# ADXL345_STEMMA_QT.net
KiCad netlist of a schematic drawn in EAGLE
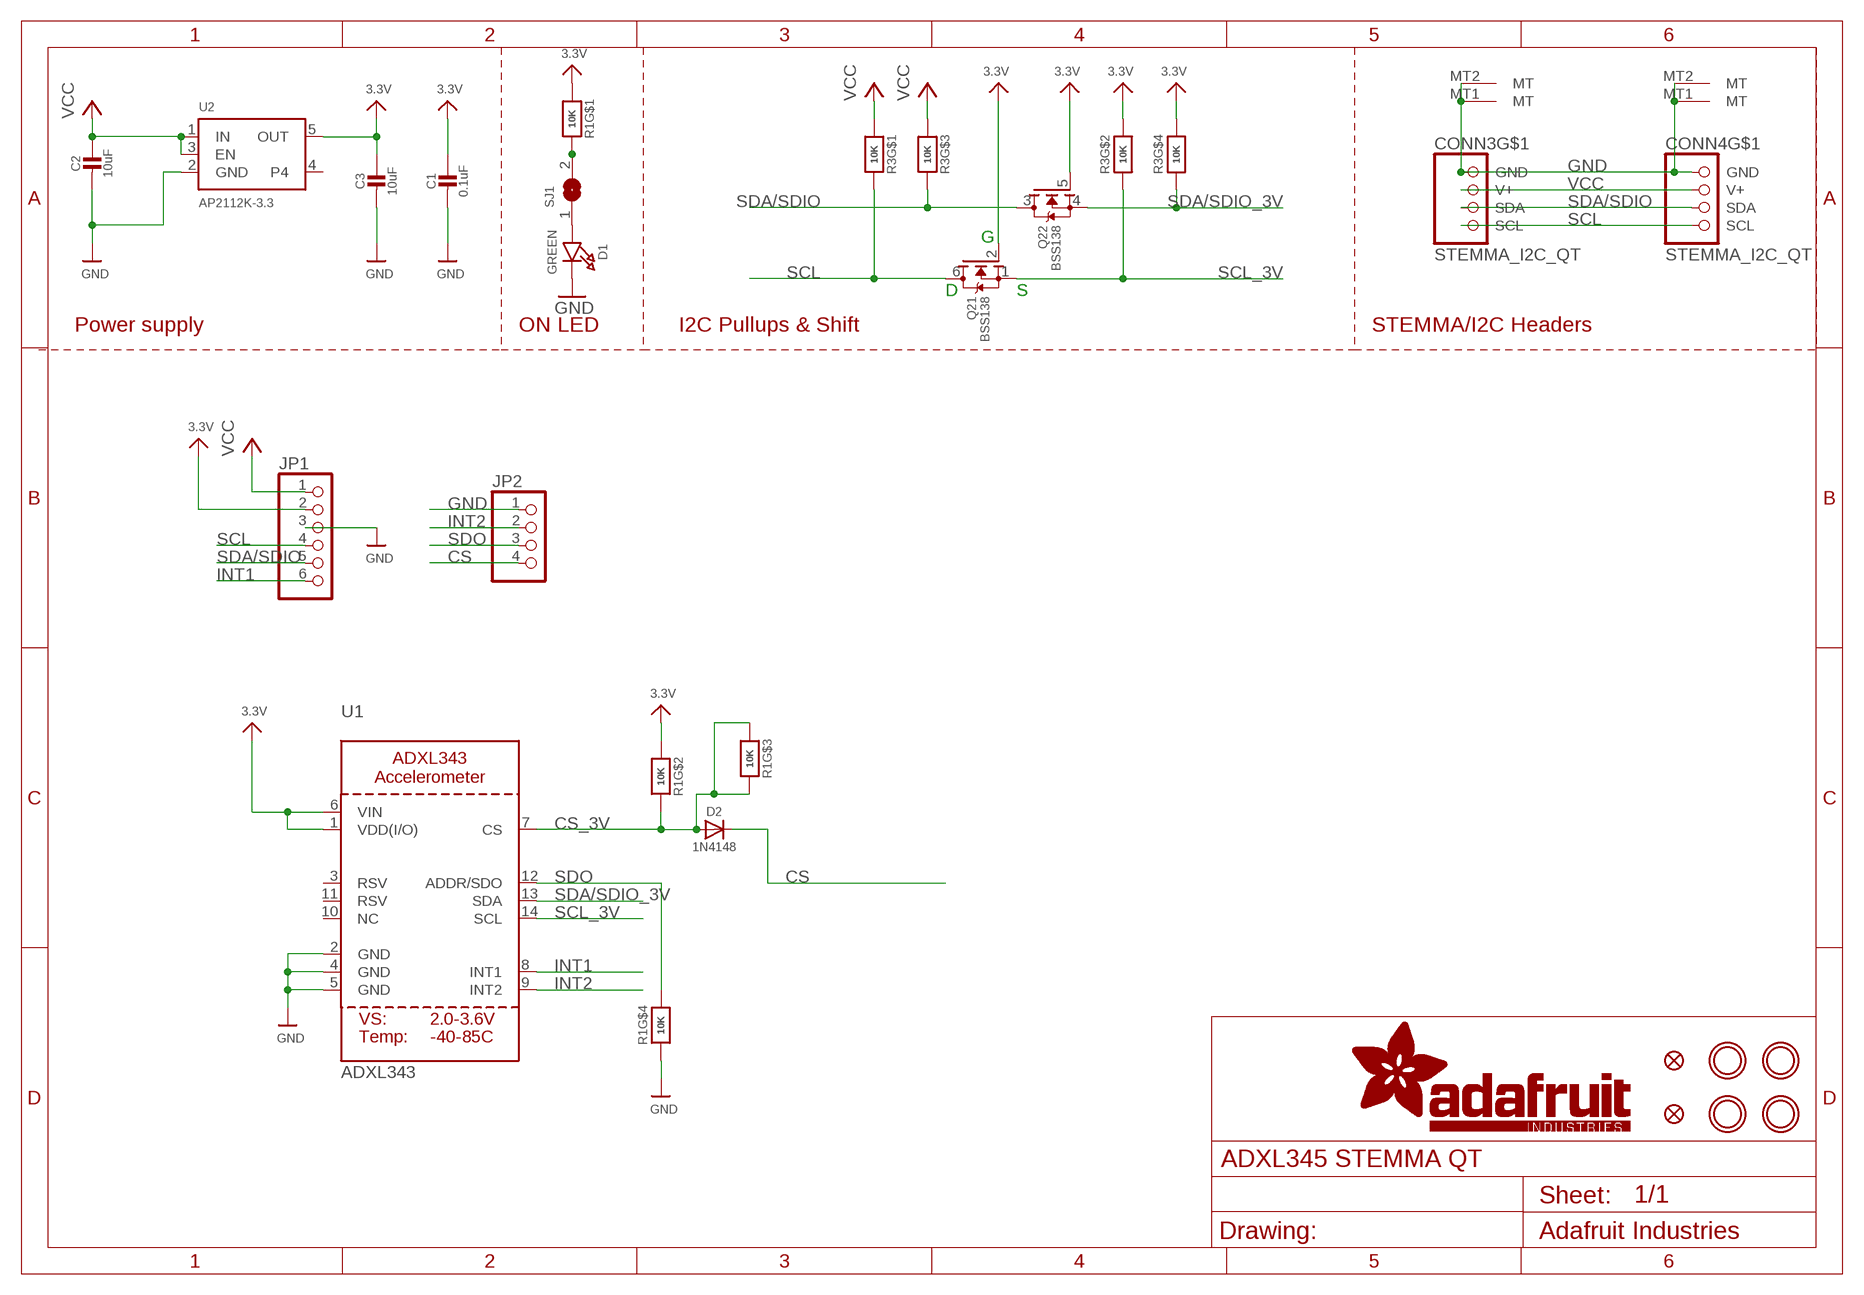
[diagram p0: schematic, sheet 1]

(export (version "E")
  (design (tool "Eeschema 10.0.6"))
  (components
    (comp (ref "C1")
      (value "0.1uF")
      (footprint "eagle-import:0603-NO")
      (libsource (lib "eagle-import") (part "CAP_CERAMIC0603_NO"))
    )
    (comp (ref "C2")
      (value "10uF")
      (footprint "eagle-import:_0805MP")
      (libsource (lib "eagle-import") (part "CAP_CERAMIC_0805MP"))
    )
    (comp (ref "C3")
      (value "10uF")
      (footprint "eagle-import:0805-NO")
      (libsource (lib "eagle-import") (part "CAP_CERAMIC0805-NOOUTLINE"))
    )
    (comp (ref "CONN3")
      (value "STEMMA_I2C_QT")
      (footprint "eagle-import:JST_SH4")
      (libsource (lib "eagle-import") (part "STEMMA_I2C_QT"))
    )
    (comp (ref "CONN4")
      (value "STEMMA_I2C_QT")
      (footprint "eagle-import:JST_SH4")
      (libsource (lib "eagle-import") (part "STEMMA_I2C_QT"))
    )
    (comp (ref "D1")
      (value "GREEN")
      (footprint "eagle-import:CHIPLED_0603_NOOUTLINE")
      (libsource (lib "eagle-import") (part "LED0603_NOOUTLINE"))
    )
    (comp (ref "D2")
      (value "1N4148")
      (footprint "eagle-import:SOD-323")
      (libsource (lib "eagle-import") (part "DIODESOD-323"))
    )
    (comp (ref "FID3")
      (value "FIDUCIAL_1MM")
      (footprint "eagle-import:FIDUCIAL_1MM")
      (libsource (lib "eagle-import") (part "FIDUCIAL_1MM"))
    )
    (comp (ref "FID4")
      (value "FIDUCIAL_1MM")
      (footprint "eagle-import:FIDUCIAL_1MM")
      (libsource (lib "eagle-import") (part "FIDUCIAL_1MM"))
    )
    (comp (ref "JP1")
      (value "HEADER-1X670MIL")
      (footprint "eagle-import:1X06_ROUND_70")
      (libsource (lib "eagle-import") (part "HEADER-1X670MIL"))
    )
    (comp (ref "JP2")
      (value "HEADER-1X4ROUND")
      (footprint "eagle-import:1X04_ROUND")
      (libsource (lib "eagle-import") (part "HEADER-1X4ROUND"))
    )
    (comp (ref "Q2")
      (value "BSS138")
      (footprint "eagle-import:SOT363")
      (libsource (lib "eagle-import") (part "MOSFET-N_DUAL"))
    )
    (comp (ref "R1")
      (value "10K")
      (footprint "eagle-import:RESPACK_4X0603")
      (libsource (lib "eagle-import") (part "RESISTOR_4PACK"))
    )
    (comp (ref "R3")
      (value "10K")
      (footprint "eagle-import:RESPACK_4X0603")
      (libsource (lib "eagle-import") (part "RESISTOR_4PACK"))
    )
    (comp (ref "SJ1")
      (value "SOLDERJUMPERCLOSED")
      (footprint "eagle-import:SOLDERJUMPER_CLOSEDWIRE")
      (libsource (lib "eagle-import") (part "SOLDERJUMPERCLOSED"))
    )
    (comp (ref "U$1")
      (value "MOUNTINGHOLE2.5")
      (footprint "eagle-import:MOUNTINGHOLE_2.5_PLATED")
      (libsource (lib "eagle-import") (part "MOUNTINGHOLE2.5"))
    )
    (comp (ref "U$17")
      (value "MOUNTINGHOLE2.5")
      (footprint "eagle-import:MOUNTINGHOLE_2.5_PLATED")
      (libsource (lib "eagle-import") (part "MOUNTINGHOLE2.5"))
    )
    (comp (ref "U$19")
      (value "MOUNTINGHOLE2.5")
      (footprint "eagle-import:MOUNTINGHOLE_2.5_PLATED")
      (libsource (lib "eagle-import") (part "MOUNTINGHOLE2.5"))
    )
    (comp (ref "U$21")
      (value "MOUNTINGHOLE2.5")
      (footprint "eagle-import:MOUNTINGHOLE_2.5_PLATED")
      (libsource (lib "eagle-import") (part "MOUNTINGHOLE2.5"))
    )
    (comp (ref "U1")
      (value "ADXL343")
      (footprint "eagle-import:LGA14")
      (libsource (lib "eagle-import") (part "ACCEL_ADXL343"))
    )
    (comp (ref "U2")
      (value "AP2112K-3.3")
      (footprint "eagle-import:SOT23-5")
      (libsource (lib "eagle-import") (part "VREG_SOT23-5"))
    )
  )
  (nets
    (net (code "1") (name "/CS") (class "Default")
      (node (ref "D2") (pin "C") (pinfunction "C_C") (pintype "passive"))
      (node (ref "JP2") (pin "4") (pinfunction "4_4") (pintype "passive"))
    )
    (net (code "2") (name "/CS_3V") (class "Default")
      (node (ref "D2") (pin "A") (pinfunction "A_A") (pintype "passive"))
      (node (ref "R1") (pin "3") (pinfunction "1_3") (pintype "passive"))
      (node (ref "R1") (pin "6") (pinfunction "2_6") (pintype "passive"))
      (node (ref "R1") (pin "7") (pinfunction "2_7") (pintype "passive"))
      (node (ref "U1") (pin "7") (pinfunction "CS_7") (pintype "bidirectional"))
    )
    (net (code "3") (name "/INT1") (class "Default")
      (node (ref "JP1") (pin "6") (pinfunction "6_6") (pintype "passive"))
      (node (ref "U1") (pin "8") (pinfunction "INT1_8") (pintype "bidirectional"))
    )
    (net (code "4") (name "/INT2") (class "Default")
      (node (ref "JP2") (pin "2") (pinfunction "2_2") (pintype "passive"))
      (node (ref "U1") (pin "9") (pinfunction "INT2_9") (pintype "bidirectional"))
    )
    (net (code "5") (name "/SCL") (class "Default")
      (node (ref "CONN3") (pin "4") (pinfunction "SCL_4") (pintype "passive"))
      (node (ref "CONN4") (pin "4") (pinfunction "SCL_4") (pintype "passive"))
      (node (ref "JP1") (pin "4") (pinfunction "4_4") (pintype "passive"))
      (node (ref "Q2") (pin "6") (pinfunction "D_6") (pintype "bidirectional"))
      (node (ref "R3") (pin "8") (pinfunction "2_8") (pintype "passive"))
    )
    (net (code "6") (name "/SCL_3V") (class "Default")
      (node (ref "Q2") (pin "1") (pinfunction "S_1") (pintype "bidirectional"))
      (node (ref "R3") (pin "7") (pinfunction "2_7") (pintype "passive"))
      (node (ref "U1") (pin "14") (pinfunction "SCL_14") (pintype "bidirectional"))
    )
    (net (code "7") (name "/SDA{slash}SDIO") (class "Default")
      (node (ref "CONN3") (pin "3") (pinfunction "SDA_3") (pintype "passive"))
      (node (ref "CONN4") (pin "3") (pinfunction "SDA_3") (pintype "passive"))
      (node (ref "JP1") (pin "5") (pinfunction "5_5") (pintype "passive"))
      (node (ref "Q2") (pin "3") (pinfunction "D_3") (pintype "bidirectional"))
      (node (ref "R3") (pin "6") (pinfunction "2_6") (pintype "passive"))
    )
    (net (code "8") (name "/SDA{slash}SDIO_3V") (class "Default")
      (node (ref "Q2") (pin "4") (pinfunction "S_4") (pintype "bidirectional"))
      (node (ref "R3") (pin "5") (pinfunction "2_5") (pintype "passive"))
      (node (ref "U1") (pin "13") (pinfunction "SDA_13") (pintype "bidirectional"))
    )
    (net (code "9") (name "/SDO") (class "Default")
      (node (ref "JP2") (pin "3") (pinfunction "3_3") (pintype "passive"))
      (node (ref "R1") (pin "5") (pinfunction "2_5") (pintype "passive"))
      (node (ref "U1") (pin "12") (pinfunction "ADDR/SDO_12") (pintype "bidirectional"))
    )
    (net (code "10") (name "3.3V") (class "Default")
      (node (ref "C1") (pin "1") (pinfunction "1_1") (pintype "passive"))
      (node (ref "C3") (pin "1") (pinfunction "1_1") (pintype "passive"))
      (node (ref "JP1") (pin "2") (pinfunction "2_2") (pintype "passive"))
      (node (ref "Q2") (pin "2") (pinfunction "G_2") (pintype "bidirectional"))
      (node (ref "Q2") (pin "5") (pinfunction "G_5") (pintype "bidirectional"))
      (node (ref "R1") (pin "1") (pinfunction "1_1") (pintype "passive"))
      (node (ref "R1") (pin "2") (pinfunction "1_2") (pintype "passive"))
      (node (ref "R3") (pin "2") (pinfunction "1_2") (pintype "passive"))
      (node (ref "R3") (pin "4") (pinfunction "1_4") (pintype "passive"))
      (node (ref "U1") (pin "1") (pinfunction "VDD(I/O)_1") (pintype "bidirectional"))
      (node (ref "U1") (pin "6") (pinfunction "VIN_6") (pintype "bidirectional"))
      (node (ref "U2") (pin "5") (pinfunction "OUT_5") (pintype "power_in"))
    )
    (net (code "11") (name "GND") (class "Default")
      (node (ref "C1") (pin "2") (pinfunction "2_2") (pintype "passive"))
      (node (ref "C2") (pin "2") (pinfunction "2_2") (pintype "passive"))
      (node (ref "C3") (pin "2") (pinfunction "2_2") (pintype "passive"))
      (node (ref "CONN3") (pin "1") (pinfunction "GND_1") (pintype "passive"))
      (node (ref "CONN3") (pin "MT1") (pinfunction "MT_MT1") (pintype "bidirectional"))
      (node (ref "CONN3") (pin "MT2") (pinfunction "MT_MT2") (pintype "bidirectional"))
      (node (ref "CONN4") (pin "1") (pinfunction "GND_1") (pintype "passive"))
      (node (ref "CONN4") (pin "MT1") (pinfunction "MT_MT1") (pintype "bidirectional"))
      (node (ref "CONN4") (pin "MT2") (pinfunction "MT_MT2") (pintype "bidirectional"))
      (node (ref "D1") (pin "C") (pinfunction "C_C") (pintype "passive"))
      (node (ref "JP1") (pin "3") (pinfunction "3_3") (pintype "passive"))
      (node (ref "JP2") (pin "1") (pinfunction "1_1") (pintype "passive"))
      (node (ref "R1") (pin "4") (pinfunction "1_4") (pintype "passive"))
      (node (ref "U1") (pin "2") (pinfunction "GND_2") (pintype "bidirectional"))
      (node (ref "U1") (pin "4") (pinfunction "GND_4") (pintype "bidirectional"))
      (node (ref "U1") (pin "5") (pinfunction "GND_5") (pintype "bidirectional"))
      (node (ref "U2") (pin "2") (pinfunction "GND_2") (pintype "power_in"))
    )
    (net (code "12") (name "Net-(D1-PadA)") (class "Default")
      (node (ref "D1") (pin "A") (pinfunction "A_A") (pintype "passive"))
      (node (ref "SJ1") (pin "1") (pinfunction "1_1") (pintype "passive"))
    )
    (net (code "13") (name "Net-(R1A-2)") (class "Default")
      (node (ref "R1") (pin "8") (pinfunction "2_8") (pintype "passive"))
      (node (ref "SJ1") (pin "2") (pinfunction "2_2") (pintype "passive"))
    )
    (net (code "14") (name "VCC") (class "Default")
      (node (ref "C2") (pin "1") (pinfunction "1_1") (pintype "passive"))
      (node (ref "CONN3") (pin "2") (pinfunction "V+_2") (pintype "passive"))
      (node (ref "CONN4") (pin "2") (pinfunction "V+_2") (pintype "passive"))
      (node (ref "JP1") (pin "1") (pinfunction "1_1") (pintype "passive"))
      (node (ref "R3") (pin "1") (pinfunction "1_1") (pintype "passive"))
      (node (ref "R3") (pin "3") (pinfunction "1_3") (pintype "passive"))
      (node (ref "U2") (pin "1") (pinfunction "IN_1") (pintype "power_in"))
      (node (ref "U2") (pin "3") (pinfunction "EN_3") (pintype "input"))
    )
    (net (code "15") (name "unconnected-(U1-NC-Pad10)") (class "Default")
      (node (ref "U1") (pin "10") (pinfunction "NC_10") (pintype "bidirectional"))
    )
    (net (code "16") (name "unconnected-(U1-RSV-Pad3)") (class "Default")
      (node (ref "U1") (pin "3") (pinfunction "RSV_3") (pintype "bidirectional"))
    )
    (net (code "17") (name "unconnected-(U1-RSV-Pad11)") (class "Default")
      (node (ref "U1") (pin "11") (pinfunction "RSV_11") (pintype "bidirectional"))
    )
    (net (code "18") (name "unconnected-(U2-P4-Pad4)") (class "Default")
      (node (ref "U2") (pin "4") (pinfunction "P4_4") (pintype "bidirectional"))
    )
  )
)
